# USB.net
KiCad netlist of a schematic drawn in Altium Designer
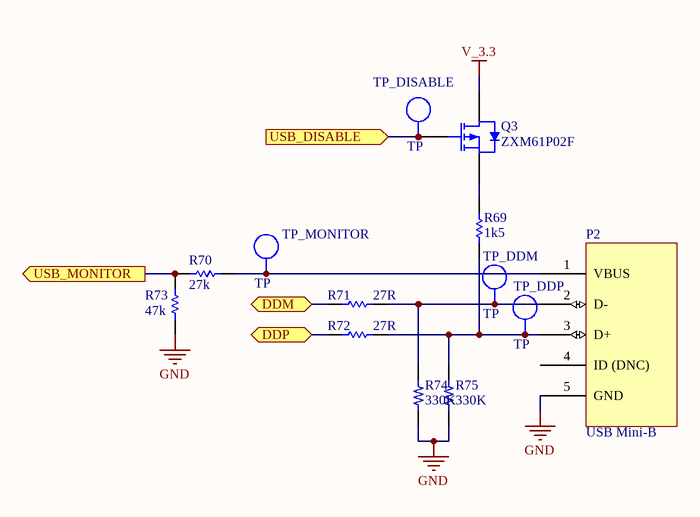
[diagram p0: USB.SchDoc]

(export (version "E")
  (design (tool "Eeschema 10.0.6"))
  (components
    (comp (ref "P2")
      (value "USB Mini-B")
      (footprint "USB Mini-B")
      (fields
        (field (name "MANUFACTURER") "TE Connectivity")
        (field (name "MANUFACTURER PART NUMBER") "1734035-2")
      )
      (libsource (lib "MarioLib") (part "USB Mini B"))
    )
    (comp (ref "Q3")
      (value "ZXM61P02F")
      (footprint "SOT23")
      (description "20V P-channel enhancement mode MOSFET")
      (fields (field (name "MANUFACTURER") "Zetex") (field (name "PART NUMBER") "TF_ZXM61P02F"))
      (libsource (lib "ENEL429_4") (part "TF_ZXM61P02F"))
    )
    (comp (ref "R69")
      (value "1k5")
      (footprint "0603")
      (description "RES 1.5K OHM 1/10W 5% 0603 SMD")
      (fields (field (name "PART NUMBER") "RS_1k5 0603") (field (name "MANUFACTURER") "Yageo"))
      (libsource (lib "ENEL429_4") (part "RS_1k5 0603"))
    )
    (comp (ref "R70")
      (value "27k")
      (footprint "0603")
      (description "RES 27K OHM 1/10W 1% 0603 SMD")
      (fields (field (name "MANUFACTURER") "Yageo") (field (name "PART NUMBER") "RS_27k 0603"))
      (libsource (lib "ENEL429_4") (part "RS_27k 0603"))
    )
    (comp (ref "R71")
      (value "27R")
      (footprint "0603")
      (description "RES 27 OHM 1/10W 1% 0603 SMD")
      (fields (field (name "PART NUMBER") "RS_27R 0603") (field (name "MANUFACTURER") "Yageo"))
      (libsource (lib "ENEL429_4") (part "RS_27R 0603"))
    )
    (comp (ref "R72")
      (value "27R")
      (footprint "0603")
      (description "RES 27 OHM 1/10W 1% 0603 SMD")
      (fields (field (name "PART NUMBER") "RS_27R 0603") (field (name "MANUFACTURER") "Yageo"))
      (libsource (lib "ENEL429_4") (part "RS_27R 0603"))
    )
    (comp (ref "R73")
      (value "47k")
      (footprint "0603")
      (description "RES 47.0K OHM 1/10W 1% 0603 SMD")
      (fields (field (name "PART NUMBER") "RS_47k 0603") (field (name "MANUFACTURER") "Yageo"))
      (libsource (lib "ENEL429_4") (part "RS_47k 0603"))
    )
    (comp (ref "R74")
      (value "330K")
      (footprint "0603 Resistor")
      (fields
        (field (name "MANUFACTURER PART NUMBER") "ERJ-3EKF3303V")
        (field (name "MANUFACTURER") "Panasonic - ECG")
      )
      (libsource (lib "MarioLib") (part "RS_330K 0603"))
    )
    (comp (ref "R75")
      (value "330K")
      (footprint "0603 Resistor")
      (fields
        (field (name "MANUFACTURER PART NUMBER") "ERJ-3EKF3303V")
        (field (name "MANUFACTURER") "Panasonic - ECG")
      )
      (libsource (lib "MarioLib") (part "RS_330K 0603"))
    )
    (comp (ref "TP_DDM")
      (value "TP")
      (footprint "TEST_POINT_4X2MM")
      (description "Test-Point")
      (fields (field (name "PART NUMBER") "TP_TESTPOINT"))
      (libsource (lib "ENEL429_4") (part "TP_TESTPOINT"))
    )
    (comp (ref "TP_DDP")
      (value "TP")
      (footprint "TEST_POINT_4X2MM")
      (description "Test-Point")
      (fields (field (name "PART NUMBER") "TP_TESTPOINT"))
      (libsource (lib "ENEL429_4") (part "TP_TESTPOINT"))
    )
    (comp (ref "TP_DISABLE")
      (value "TP")
      (footprint "TEST_POINT_4X2MM")
      (description "Test-Point")
      (fields (field (name "PART NUMBER") "TP_TESTPOINT"))
      (libsource (lib "ENEL429_4") (part "TP_TESTPOINT"))
    )
    (comp (ref "TP_MONITOR")
      (value "TP")
      (footprint "TEST_POINT_4X2MM")
      (description "Test-Point")
      (fields (field (name "PART NUMBER") "TP_TESTPOINT"))
      (libsource (lib "ENEL429_4") (part "TP_TESTPOINT"))
    )
  )
  (nets
    (net (code "1") (name "/DDM") (class "Default")
      (node (ref "R71") (pin "1") (pinfunction "1_1") (pintype "passive"))
    )
    (net (code "2") (name "/DDP") (class "Default")
      (node (ref "R72") (pin "1") (pinfunction "1_1") (pintype "passive"))
    )
    (net (code "3") (name "/USB_DISABLE") (class "Default")
      (node (ref "Q3") (pin "1") (pinfunction "G_1") (pintype "passive"))
      (node (ref "TP_DISABLE") (pin "1") (pinfunction "1_1") (pintype "passive"))
    )
    (net (code "4") (name "/USB_MONITOR") (class "Default")
      (node (ref "R70") (pin "1") (pinfunction "1_1") (pintype "passive"))
      (node (ref "R73") (pin "2") (pinfunction "2_2") (pintype "passive"))
    )
    (net (code "5") (name "GND") (class "Default")
      (node (ref "P2") (pin "5") (pinfunction "GND_5") (pintype "passive"))
      (node (ref "R73") (pin "1") (pinfunction "1_1") (pintype "passive"))
      (node (ref "R74") (pin "1") (pinfunction "1_1") (pintype "passive"))
      (node (ref "R75") (pin "1") (pinfunction "1_1") (pintype "passive"))
    )
    (net (code "6") (name "Net-(P2-D+)") (class "Default")
      (node (ref "P2") (pin "3") (pinfunction "D+_3") (pintype "bidirectional"))
      (node (ref "R69") (pin "1") (pinfunction "1_1") (pintype "passive"))
      (node (ref "R72") (pin "2") (pinfunction "2_2") (pintype "passive"))
      (node (ref "R75") (pin "2") (pinfunction "2_2") (pintype "passive"))
      (node (ref "TP_DDP") (pin "1") (pinfunction "1_1") (pintype "passive"))
    )
    (net (code "7") (name "Net-(P2-D-)") (class "Default")
      (node (ref "P2") (pin "2") (pinfunction "D-_2") (pintype "bidirectional"))
      (node (ref "R71") (pin "2") (pinfunction "2_2") (pintype "passive"))
      (node (ref "R74") (pin "2") (pinfunction "2_2") (pintype "passive"))
      (node (ref "TP_DDM") (pin "1") (pinfunction "1_1") (pintype "passive"))
    )
    (net (code "8") (name "Net-(P2-VBUS)") (class "Default")
      (node (ref "P2") (pin "1") (pinfunction "VBUS_1") (pintype "power_in"))
      (node (ref "R70") (pin "2") (pinfunction "2_2") (pintype "passive"))
      (node (ref "TP_MONITOR") (pin "1") (pinfunction "1_1") (pintype "passive"))
    )
    (net (code "9") (name "Net-(Q3-S)") (class "Default")
      (node (ref "Q3") (pin "2") (pinfunction "S_2") (pintype "passive"))
      (node (ref "R69") (pin "2") (pinfunction "2_2") (pintype "passive"))
    )
    (net (code "10") (name "V_3.3") (class "Default")
      (node (ref "Q3") (pin "3") (pinfunction "D_3") (pintype "passive"))
    )
    (net (code "11") (name "unconnected-(P2-ID_(DNC)-Pad4)") (class "Default")
      (node (ref "P2") (pin "4") (pinfunction "ID_(DNC)_4") (pintype "passive"))
    )
  )
)
